# 51-2001-01-16_04_Power_Module_Schematic.net
KiCad netlist of a schematic drawn in Altium Designer
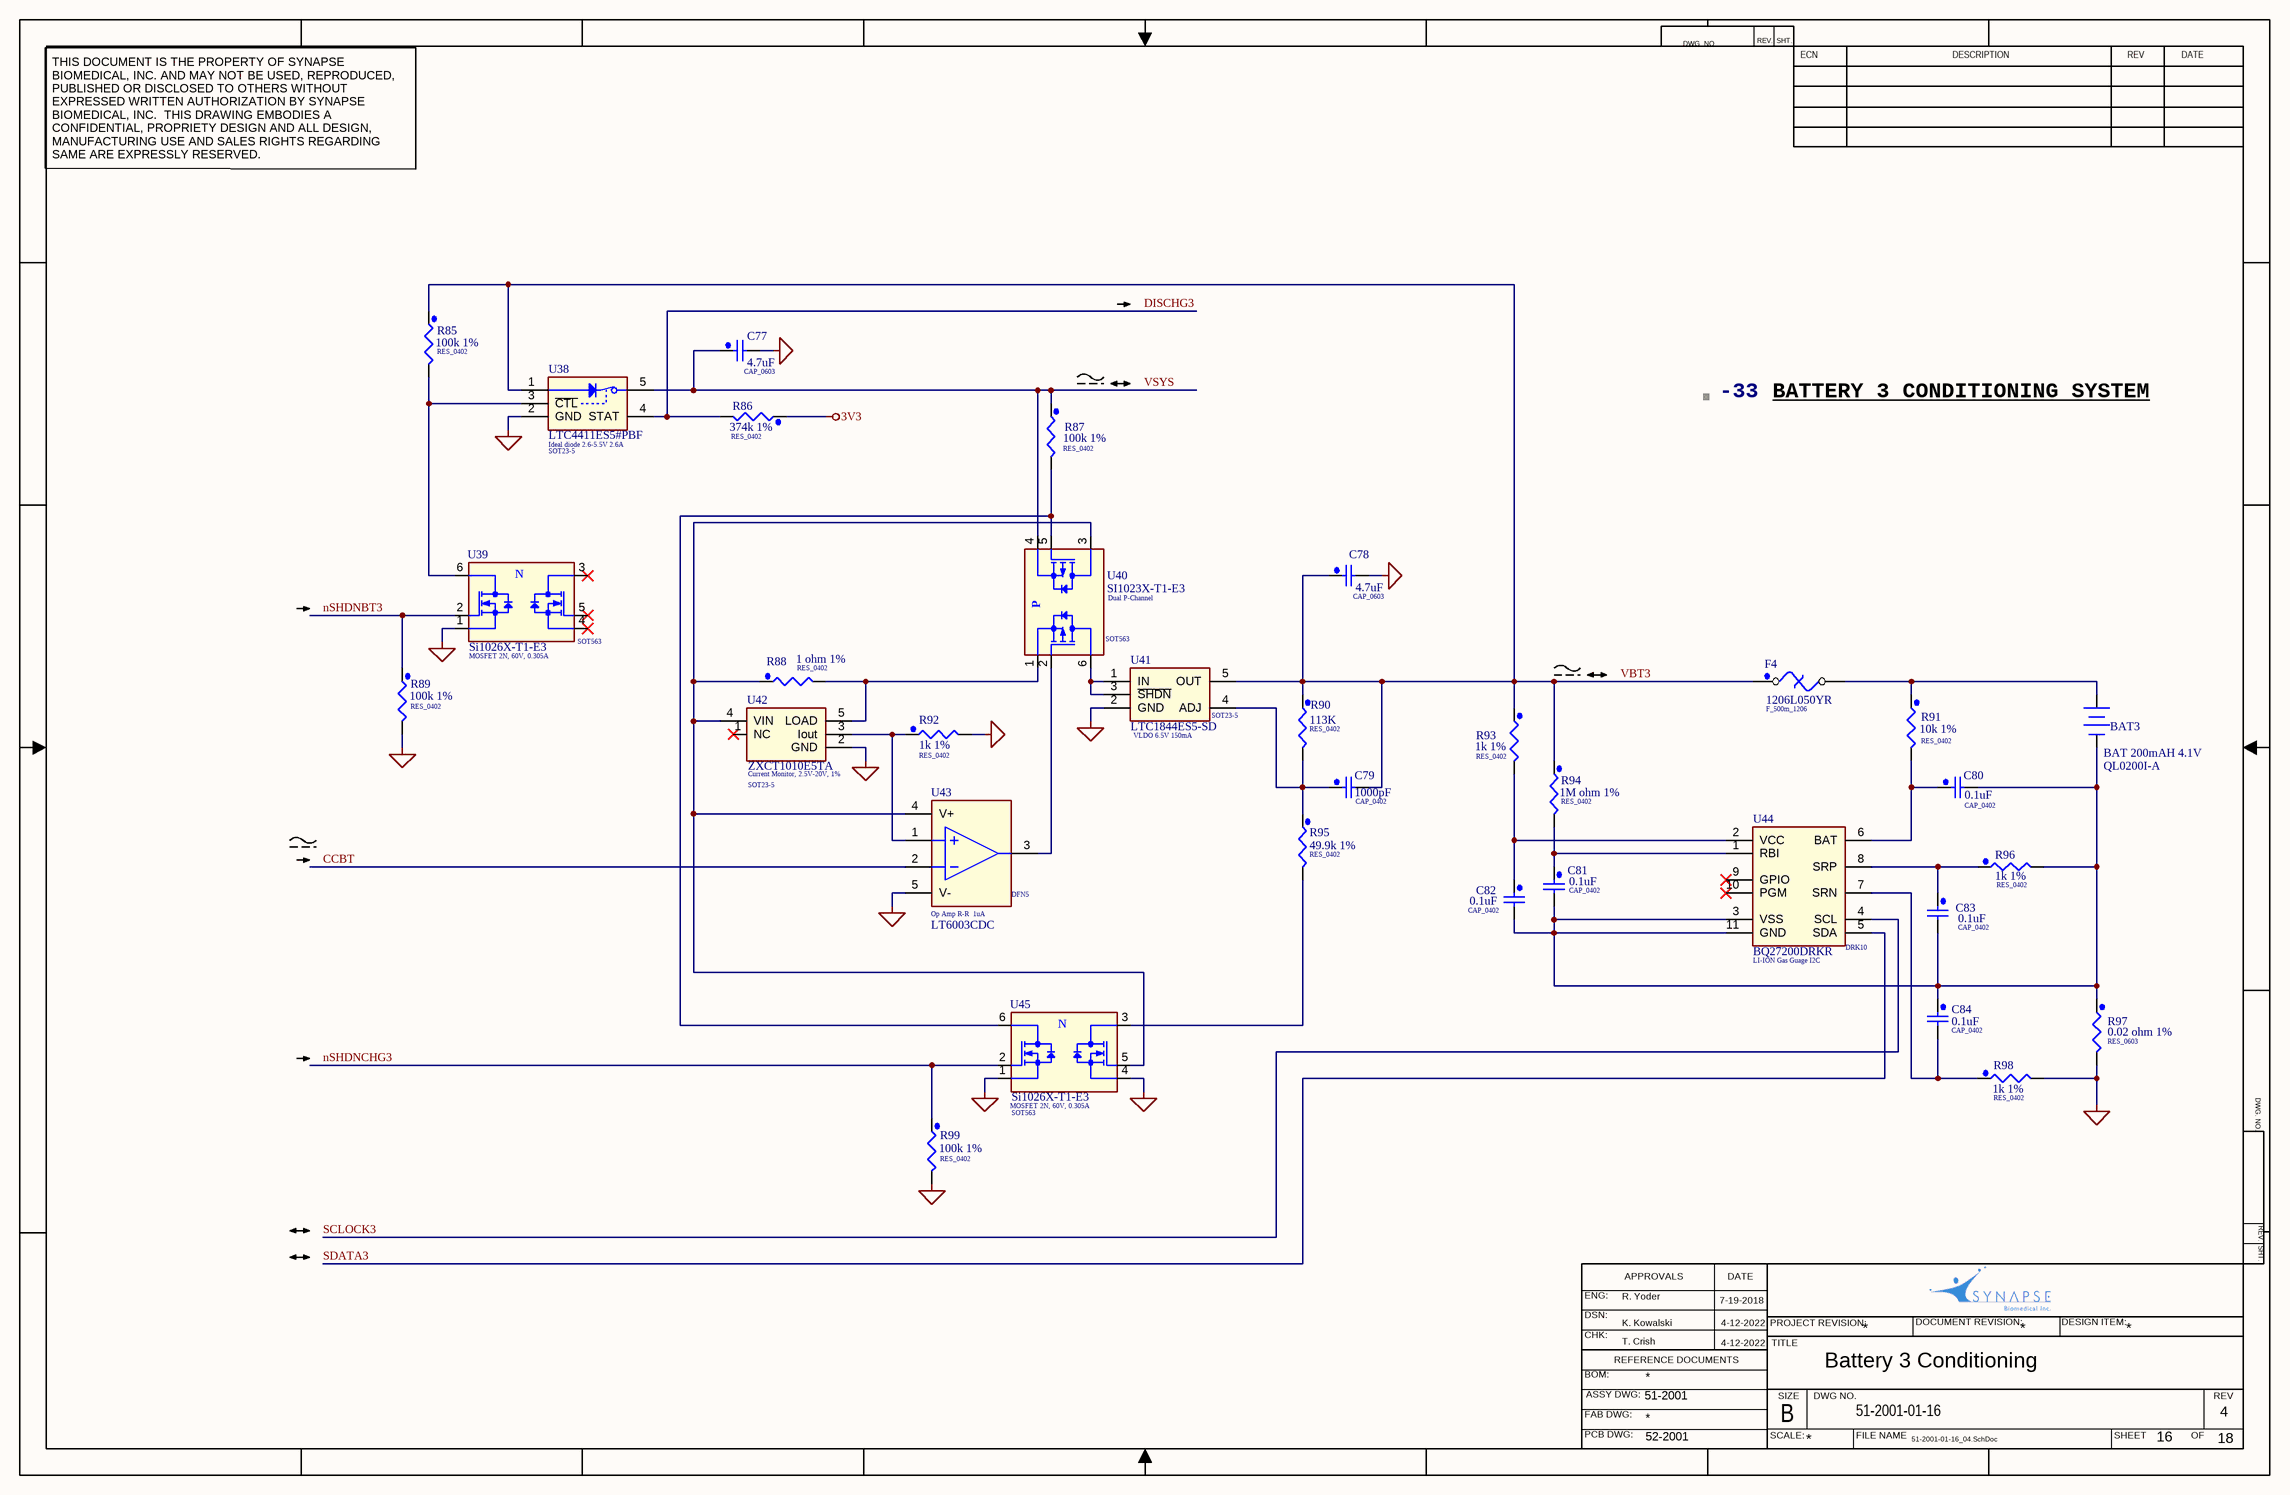
[diagram p0: 51-2001-01-16_04 Power Module Schematic.SchDoc]

(export (version "E")
  (design (tool "Eeschema 10.0.6"))
  (components
    (comp (ref "-33")
      (value "BOM_S1")
      (description "BOM item small graphic")
      (fields (field (name "XDESCRIPTION") "BATTERY 3 CONDITIONING SYSTEM"))
      (libsource (lib "BOM_sym") (part "BOM_S1"))
    )
    (comp (ref "BAT3")
      (value "BAT 200mAH 4.1V")
      (footprint "QL0200I-A")
      (description "Li-ion battery 200mAH 4.1V")
      (fields (field (name "MFR") "Quallion") (field (name "MPN") "QL0200I-A"))
      (libsource (lib "NNPS Integrated Parts") (part "QL0200I-A"))
    )
    (comp (ref "C77")
      (value "4.7uF")
      (footprint "CAP_0603")
      (description "4.7uF, 10V, X5R, 10%, 0603, RoHS")
      (fields
        (field (name "MFR") "Murata Electronics North America")
        (field (name "PACKAGEDESCRIPTION") "CAP_0603")
        (field (name "MPN") "GRM185R61A475KE11D")
      )
      (libsource (lib "NNPS Integrated Parts") (part "LMK107BJ475KA-T"))
    )
    (comp (ref "C78")
      (value "4.7uF")
      (footprint "CAP_0603")
      (description "4.7uF, 10V, X5R, 10%, 0603, RoHS")
      (fields
        (field (name "MFR") "Murata Electronics North America")
        (field (name "PACKAGEDESCRIPTION") "CAP_0603")
        (field (name "MPN") "GRM185R61A475KE11D")
      )
      (libsource (lib "NNPS Integrated Parts") (part "LMK107BJ475KA-T"))
    )
    (comp (ref "C79")
      (value "1000pF")
      (footprint "CAP_0402")
      (description "1000pF, 50V, C0G, 5%, 0402, RoHS")
      (fields
        (field (name "MFR") "Murata")
        (field (name "PACKAGEDESCRIPTION") "CAP_0402")
        (field (name "MPN") "GRM1555C1H102JA01D")
      )
      (libsource (lib "NNPS Integrated Parts") (part "GRM1555C1H102JA01D"))
    )
    (comp (ref "C80")
      (value "0.1uF")
      (footprint "CAP_0402")
      (description "0.1uF, 16V, X7R, 0402, RoHS")
      (fields
        (field (name "MFR") "Murata")
        (field (name "PACKAGEDESCRIPTION") "CAP_0402")
        (field (name "MPN") "GRM155R71C104KA88D")
      )
      (libsource (lib "NNPS Integrated Parts") (part "GRM155R71C104KA88D"))
    )
    (comp (ref "C81")
      (value "0.1uF")
      (footprint "CAP_0402")
      (description "0.1uF, 16V, X7R, 0402, RoHS")
      (fields
        (field (name "MFR") "Murata")
        (field (name "PACKAGEDESCRIPTION") "CAP_0402")
        (field (name "MPN") "GRM155R71C104KA88D")
      )
      (libsource (lib "NNPS Integrated Parts") (part "GRM155R71C104KA88D"))
    )
    (comp (ref "C82")
      (value "0.1uF")
      (footprint "CAP_0402")
      (description "0.1uF, 16V, X7R, 0402, RoHS")
      (fields
        (field (name "MFR") "Murata")
        (field (name "PACKAGEDESCRIPTION") "CAP_0402")
        (field (name "MPN") "GRM155R71C104KA88D")
      )
      (libsource (lib "NNPS Integrated Parts") (part "GRM155R71C104KA88D"))
    )
    (comp (ref "C83")
      (value "0.1uF")
      (footprint "CAP_0402")
      (description "0.1uF, 16V, X7R, 0402, RoHS")
      (fields
        (field (name "MFR") "Murata")
        (field (name "PACKAGEDESCRIPTION") "CAP_0402")
        (field (name "MPN") "GRM155R71C104KA88D")
      )
      (libsource (lib "NNPS Integrated Parts") (part "GRM155R71C104KA88D"))
    )
    (comp (ref "C84")
      (value "0.1uF")
      (footprint "CAP_0402")
      (description "0.1uF, 16V, X7R, 0402, RoHS")
      (fields
        (field (name "MFR") "Murata")
        (field (name "PACKAGEDESCRIPTION") "CAP_0402")
        (field (name "MPN") "GRM155R71C104KA88D")
      )
      (libsource (lib "NNPS Integrated Parts") (part "GRM155R71C104KA88D"))
    )
    (comp (ref "F4")
      (value "F_500m_1206")
      (footprint "FUSE_1206")
      (description "PTC Resettable, 500mA, 0.4 ohm,  6V, 1206, RoHS")
      (fields
        (field (name "MFR") "Littelfuse")
        (field (name "PACKAGEDESCRIPTION") "F_500m_1206")
        (field (name "MPN") "1206L050YR")
      )
      (libsource (lib "NNPS Integrated Parts") (part "1206L050YR"))
    )
    (comp (ref "R85")
      (value "100k 1%")
      (footprint "RES_0402")
      (description "100k ohm, 1%, 1/16W, smd, 0402, RoHS")
      (fields
        (field (name "MFR") "Vishay Dale")
        (field (name "PACKAGEDESCRIPTION") "RES_0402")
        (field (name "MPN") "CRCW0402100KFKED")
      )
      (libsource (lib "NNPS Integrated Parts") (part "MCR01MZPF1003"))
    )
    (comp (ref "R86")
      (value "374k 1%")
      (footprint "RES_0402")
      (description "374k ohm, 1%, 1/16W, 0402,RoHS")
      (fields
        (field (name "MFR") "Vishay Dale")
        (field (name "PACKAGEDESCRIPTION") "RES_0402")
        (field (name "MPN") "CRCW0402374KFKED")
      )
      (libsource (lib "NNPS Integrated Parts") (part "CRCW0402374KFKED"))
    )
    (comp (ref "R87")
      (value "100k 1%")
      (footprint "RES_0402")
      (description "100k ohm, 1%, 1/16W, smd, 0402, RoHS")
      (fields
        (field (name "MFR") "Vishay Dale")
        (field (name "PACKAGEDESCRIPTION") "RES_0402")
        (field (name "MPN") "CRCW0402100KFKED")
      )
      (libsource (lib "NNPS Integrated Parts") (part "MCR01MZPF1003"))
    )
    (comp (ref "R88")
      (value "1 ohm 1%")
      (footprint "RES_0402")
      (description "1.0 ohm, 1%, 1/16W, 0402, RoHS")
      (fields
        (field (name "MFR") "Vishay Dale")
        (field (name "PACKAGEDESCRIPTION") "RES_0402")
        (field (name "MPN") "CRCW04021R00FNED")
      )
      (libsource (lib "NNPS Integrated Parts") (part "CRCW04021R00FNED"))
    )
    (comp (ref "R89")
      (value "100k 1%")
      (footprint "RES_0402")
      (description "100k ohm, 1%, 1/16W, smd, 0402, RoHS")
      (fields
        (field (name "MFR") "Vishay Dale")
        (field (name "PACKAGEDESCRIPTION") "RES_0402")
        (field (name "MPN") "CRCW0402100KFKED")
      )
      (libsource (lib "NNPS Integrated Parts") (part "MCR01MZPF1003"))
    )
    (comp (ref "R90")
      (value "113K")
      (footprint "RES_0402")
      (description "113k ohm, 1%, 1/16W, 0402, RoHS")
      (fields
        (field (name "MFR") "Vishay Dale")
        (field (name "PACKAGEDESCRIPTION") "RES_0402")
        (field (name "MPN") "CRCW0402113KFKED")
      )
      (libsource (lib "NNPS Integrated Parts") (part "ERJ-2RKF1133X"))
    )
    (comp (ref "R91")
      (value "10k 1%")
      (footprint "RES_0402")
      (description "10.0k ohm, 1%, 1/16W, smd, 0402, RoHS")
      (fields
        (field (name "MFR") "Vishay Dale")
        (field (name "PACKAGEDESCRIPTION") "RES_0402")
        (field (name "MPN") "CRCW040210K0FKED")
      )
      (libsource (lib "NNPS Integrated Parts") (part "MCR01MZPF1002"))
    )
    (comp (ref "R92")
      (value "1k 1%")
      (footprint "RES_0402")
      (description "1.0k ohm 1% 1/16W smd 0402 RoHS")
      (fields
        (field (name "MFR") "Vishay Dale")
        (field (name "PACKAGEDESCRIPTION") "RES_0402")
        (field (name "MPN") "CRCW04021K00FKED")
      )
      (libsource (lib "NNPS Integrated Parts") (part "MCR01MZPF1001"))
    )
    (comp (ref "R93")
      (value "1k 1%")
      (footprint "RES_0402")
      (description "1.0k ohm 1% 1/16W smd 0402 RoHS")
      (fields
        (field (name "MFR") "Vishay Dale")
        (field (name "PACKAGEDESCRIPTION") "RES_0402")
        (field (name "MPN") "CRCW04021K00FKED")
      )
      (libsource (lib "NNPS Integrated Parts") (part "MCR01MZPF1001"))
    )
    (comp (ref "R94")
      (value "1M ohm 1%")
      (footprint "RES_0402")
      (description "1M ohm, 1/16W, 1%, 0402, RoHS")
      (fields
        (field (name "MFR") "Vishay Dale")
        (field (name "PACKAGEDESCRIPTION") "RES_0402")
        (field (name "MPN") "CRCW04021M00FKED")
      )
      (libsource (lib "NNPS Integrated Parts") (part "MCR01MZPF1004"))
    )
    (comp (ref "R95")
      (value "49.9k 1%")
      (footprint "RES_0402")
      (description "49.9k ohm, 1%, 1/16W, 0402, RoHS")
      (fields
        (field (name "MFR") "Vishay Dale")
        (field (name "PACKAGEDESCRIPTION") "RES_0402")
        (field (name "MPN") "CRCW040249K9FKED")
      )
      (libsource (lib "NNPS Integrated Parts") (part "MCR01MZPF4992"))
    )
    (comp (ref "R96")
      (value "1k 1%")
      (footprint "RES_0402")
      (description "1.0k ohm 1% 1/16W smd 0402 RoHS")
      (fields
        (field (name "MFR") "Vishay Dale")
        (field (name "PACKAGEDESCRIPTION") "RES_0402")
        (field (name "MPN") "CRCW04021K00FKED")
      )
      (libsource (lib "NNPS Integrated Parts") (part "MCR01MZPF1001"))
    )
    (comp (ref "R97")
      (value "0.02 ohm 1%")
      (footprint "RES_0603")
      (description "0.02 ohm, 1%, 1/10W, 0603, RoHS")
      (fields
        (field (name "MFR") "Vishay Dale")
        (field (name "PACKAGEDESCRIPTION") "RES_0603")
        (field (name "MPN") "WSL0603R0200FEA")
      )
      (libsource (lib "NNPS Integrated Parts") (part "WSL0603R0200FEA"))
    )
    (comp (ref "R98")
      (value "1k 1%")
      (footprint "RES_0402")
      (description "1.0k ohm 1% 1/16W smd 0402 RoHS")
      (fields
        (field (name "MFR") "Vishay Dale")
        (field (name "PACKAGEDESCRIPTION") "RES_0402")
        (field (name "MPN") "CRCW04021K00FKED")
      )
      (libsource (lib "NNPS Integrated Parts") (part "MCR01MZPF1001"))
    )
    (comp (ref "R99")
      (value "100k 1%")
      (footprint "RES_0402")
      (description "100k ohm, 1%, 1/16W, smd, 0402, RoHS")
      (fields
        (field (name "MFR") "Vishay Dale")
        (field (name "PACKAGEDESCRIPTION") "RES_0402")
        (field (name "MPN") "CRCW0402100KFKED")
      )
      (libsource (lib "NNPS Integrated Parts") (part "MCR01MZPF1003"))
    )
    (comp (ref "U38")
      (value "Ideal diode 2.6-5.5V 2.6A")
      (footprint "SOT23-5")
      (description "Ideal diode, 2.6-5.5V, 2.6A, SOT23-5, RoHS")
      (fields
        (field (name "MFR") "Linear Technology")
        (field (name "PACKAGEDESCRIPTION") "SOT23-5")
        (field (name "MPN") "LTC4411ES5#PBF")
      )
      (libsource (lib "NNPS Integrated Parts") (part "LTC4411ES5"))
    )
    (comp (ref "U39")
      (value "MOSFET 2N, 60V, 0.305A")
      (footprint "SOT-563")
      (description "MOSFET 2N, 60V, 0.305A, RoHS")
      (fields
        (field (name "MFR") "Vishay Siliconix")
        (field (name "PACKAGEDESCRIPTION") "SOT563")
        (field (name "MPN") "Si1026X-T1-E3")
      )
      (libsource (lib "NNPS Integrated Parts") (part "Si1026X-T1-E3"))
    )
    (comp (ref "U40")
      (value "Dual P-Channel")
      (footprint "SOT-563")
      (description "Dual P-Channel Mosfet, SOT563, RoHS")
      (fields
        (field (name "MFR") "Vishay Siliconix")
        (field (name "PACKAGEDESCRIPTION") "SOT563")
        (field (name "MPN") "SI1023X-T1-E3")
      )
      (libsource (lib "NNPS Integrated Parts") (part "SI1023X-T1-E3"))
    )
    (comp (ref "U41")
      (value "VLDO 6.5V 150mA")
      (footprint "SOT23-5")
      (description "VLDO, 150mA, SOT23-5, RoHS")
      (fields
        (field (name "MFR") "Linear Technology")
        (field (name "PACKAGEDESCRIPTION") "SOT23-5")
        (field (name "MPN") "LTC1844ES5-SD")
      )
      (libsource (lib "NNPS Integrated Parts") (part "LTC1844ES5-SD"))
    )
    (comp (ref "U42")
      (value "Current Monitor, 2.5V-20V, 1%")
      (footprint "SOT23-5")
      (description "Current Monitor, 2.5V-20V, 1%, RoHS")
      (fields
        (field (name "MFR") "Diodes Incorporated")
        (field (name "PACKAGEDESCRIPTION") "SOT23-5")
        (field (name "MPN") "ZXCT1010E5TA")
      )
      (libsource (lib "NNPS Integrated Parts") (part "ZXCT1010E5TA"))
    )
    (comp (ref "U43")
      (value "Op Amp R-R  1uA")
      (footprint "DFN4")
      (description "Op Amp, R-R, 1uA, RoHS")
      (fields
        (field (name "PACKAGEDESCRIPTION") "DFN5")
        (field (name "MFR") "Linear Technology")
        (field (name "MPN") "LT6003CDC")
      )
      (libsource (lib "NNPS Integrated Parts") (part "LT6003CDC"))
    )
    (comp (ref "U44")
      (value "LI-ION Gas Guage I2C")
      (footprint "QFN10")
      (description "LI-ION Gas Guage, I2C, QFN10, RoHS")
      (fields
        (field (name "MFR") "Texas Instruments")
        (field (name "PACKAGEDESCRIPTION") "DRK10")
        (field (name "MPN") "BQ27200DRKR")
      )
      (libsource (lib "NNPS Integrated Parts") (part "BQ27200DRKR"))
    )
    (comp (ref "U45")
      (value "MOSFET 2N, 60V, 0.305A")
      (footprint "SOT-563")
      (description "MOSFET 2N, 60V, 0.305A, RoHS")
      (fields
        (field (name "MFR") "Vishay Siliconix")
        (field (name "PACKAGEDESCRIPTION") "SOT563")
        (field (name "MPN") "Si1026X-T1-E3")
      )
      (libsource (lib "NNPS Integrated Parts") (part "Si1026X-T1-E3"))
    )
  )
  (nets
    (net (code "1") (name "/CCBT") (class "Default")
      (node (ref "U43") (pin "2") (pinfunction "-IN_2") (pintype "passive"))
    )
    (net (code "2") (name "/DISCHG3") (class "Default")
      (node (ref "R86") (pin "2") (pinfunction "2_2") (pintype "passive"))
      (node (ref "U38") (pin "4") (pinfunction "STAT_4") (pintype "passive"))
    )
    (net (code "3") (name "/SCLOCK3") (class "Default")
      (node (ref "U44") (pin "4") (pinfunction "SCL_4") (pintype "passive"))
    )
    (net (code "4") (name "/SDATA3") (class "Default")
      (node (ref "U44") (pin "5") (pinfunction "SDA_5") (pintype "passive"))
    )
    (net (code "5") (name "/VBT3") (class "Default")
      (node (ref "C78") (pin "1") (pinfunction "1_1") (pintype "passive"))
      (node (ref "C79") (pin "2") (pinfunction "2_2") (pintype "passive"))
      (node (ref "F4") (pin "1") (pinfunction "1_1") (pintype "passive"))
      (node (ref "R85") (pin "1") (pinfunction "1_1") (pintype "passive"))
      (node (ref "R90") (pin "1") (pinfunction "1_1") (pintype "passive"))
      (node (ref "R93") (pin "1") (pinfunction "1_1") (pintype "passive"))
      (node (ref "R94") (pin "1") (pinfunction "1_1") (pintype "passive"))
      (node (ref "U38") (pin "1") (pinfunction "IN_1") (pintype "passive"))
      (node (ref "U41") (pin "5") (pinfunction "OUT_5") (pintype "passive"))
    )
    (net (code "6") (name "/VSYS") (class "Default")
      (node (ref "C77") (pin "1") (pinfunction "1_1") (pintype "passive"))
      (node (ref "R87") (pin "1") (pinfunction "1_1") (pintype "passive"))
      (node (ref "U38") (pin "5") (pinfunction "OUT_5") (pintype "passive"))
      (node (ref "U40") (pin "4") (pinfunction "S2_4") (pintype "passive"))
    )
    (net (code "7") (name "/nSHDNBT3") (class "Default")
      (node (ref "R89") (pin "1") (pinfunction "1_1") (pintype "passive"))
      (node (ref "U39") (pin "2") (pinfunction "G1_2") (pintype "passive"))
    )
    (net (code "8") (name "/nSHDNCHG3") (class "Default")
      (node (ref "R99") (pin "1") (pinfunction "1_1") (pintype "passive"))
      (node (ref "U45") (pin "2") (pinfunction "G1_2") (pintype "passive"))
    )
    (net (code "9") (name "3V3") (class "Default")
      (node (ref "R86") (pin "1") (pinfunction "1_1") (pintype "passive"))
    )
    (net (code "10") (name "<NO NET>") (class "Default")
      (node (ref "R99") (pin "2") (pinfunction "2_2") (pintype "passive"))
    )
    (net (code "11") (name "GND") (class "Default")
      (node (ref "C77") (pin "2") (pinfunction "2_2") (pintype "passive"))
      (node (ref "C78") (pin "2") (pinfunction "2_2") (pintype "passive"))
      (node (ref "R89") (pin "2") (pinfunction "2_2") (pintype "passive"))
      (node (ref "R92") (pin "2") (pinfunction "2_2") (pintype "passive"))
      (node (ref "R97") (pin "2") (pinfunction "2_2") (pintype "passive"))
      (node (ref "R98") (pin "2") (pinfunction "2_2") (pintype "passive"))
      (node (ref "U38") (pin "2") (pinfunction "GND_2") (pintype "passive"))
      (node (ref "U39") (pin "1") (pinfunction "S1_1") (pintype "passive"))
      (node (ref "U41") (pin "2") (pinfunction "GND_2") (pintype "passive"))
      (node (ref "U42") (pin "2") (pinfunction "GND_2") (pintype "power_in"))
      (node (ref "U43") (pin "5") (pinfunction "V-_5") (pintype "power_in"))
      (node (ref "U45") (pin "1") (pinfunction "S1_1") (pintype "passive"))
      (node (ref "U45") (pin "4") (pinfunction "S2_4") (pintype "passive"))
    )
    (net (code "12") (name "Net-(BAT3-+)") (class "Default")
      (node (ref "BAT3") (pin "1") (pinfunction "+_1") (pintype "passive"))
      (node (ref "F4") (pin "2") (pinfunction "2_2") (pintype "passive"))
      (node (ref "R91") (pin "1") (pinfunction "1_1") (pintype "passive"))
    )
    (net (code "13") (name "Net-(BAT3--)") (class "Default")
      (node (ref "BAT3") (pin "2") (pinfunction "-_2") (pintype "passive"))
      (node (ref "C80") (pin "2") (pinfunction "2_2") (pintype "passive"))
      (node (ref "C81") (pin "2") (pinfunction "2_2") (pintype "passive"))
      (node (ref "C82") (pin "2") (pinfunction "2_2") (pintype "passive"))
      (node (ref "C83") (pin "2") (pinfunction "2_2") (pintype "passive"))
      (node (ref "C84") (pin "1") (pinfunction "1_1") (pintype "passive"))
      (node (ref "R96") (pin "2") (pinfunction "2_2") (pintype "passive"))
      (node (ref "R97") (pin "1") (pinfunction "1_1") (pintype "passive"))
      (node (ref "U44") (pin "11") (pinfunction "GND_11") (pintype "passive"))
      (node (ref "U44") (pin "3") (pinfunction "VSS_3") (pintype "passive"))
    )
    (net (code "14") (name "Net-(U38-~{CTL})") (class "Default")
      (node (ref "R85") (pin "2") (pinfunction "2_2") (pintype "passive"))
      (node (ref "U38") (pin "3") (pinfunction "~{CTL}_3") (pintype "passive"))
      (node (ref "U39") (pin "6") (pinfunction "D1_6") (pintype "passive"))
    )
    (net (code "15") (name "Net-(U40-D1)") (class "Default")
      (node (ref "U40") (pin "6") (pinfunction "D1_6") (pintype "passive"))
      (node (ref "U41") (pin "1") (pinfunction "IN_1") (pintype "passive"))
      (node (ref "U41") (pin "3") (pinfunction "SHDN_3") (pintype "passive"))
    )
    (net (code "16") (name "Net-(U40-D2)") (class "Default")
      (node (ref "R88") (pin "1") (pinfunction "1_1") (pintype "passive"))
      (node (ref "U40") (pin "3") (pinfunction "D2_3") (pintype "passive"))
      (node (ref "U42") (pin "4") (pinfunction "VIN_4") (pintype "power_in"))
      (node (ref "U43") (pin "4") (pinfunction "V+_4") (pintype "power_in"))
      (node (ref "U45") (pin "5") (pinfunction "G2_5") (pintype "passive"))
    )
    (net (code "17") (name "Net-(U40-G1)") (class "Default")
      (node (ref "U40") (pin "2") (pinfunction "G1_2") (pintype "passive"))
      (node (ref "U43") (pin "3") (pinfunction "OUT_A_3") (pintype "passive"))
    )
    (net (code "18") (name "Net-(U40-G2)") (class "Default")
      (node (ref "R87") (pin "2") (pinfunction "2_2") (pintype "passive"))
      (node (ref "U40") (pin "5") (pinfunction "G2_5") (pintype "passive"))
      (node (ref "U45") (pin "6") (pinfunction "D1_6") (pintype "passive"))
    )
    (net (code "19") (name "Net-(U40-S1)") (class "Default")
      (node (ref "R88") (pin "2") (pinfunction "2_2") (pintype "passive"))
      (node (ref "U40") (pin "1") (pinfunction "S1_1") (pintype "passive"))
      (node (ref "U42") (pin "5") (pinfunction "LOAD_5") (pintype "passive"))
    )
    (net (code "20") (name "Net-(U41-ADJ)") (class "Default")
      (node (ref "C79") (pin "1") (pinfunction "1_1") (pintype "passive"))
      (node (ref "R90") (pin "2") (pinfunction "2_2") (pintype "passive"))
      (node (ref "R95") (pin "1") (pinfunction "1_1") (pintype "passive"))
      (node (ref "U41") (pin "4") (pinfunction "ADJ_4") (pintype "passive"))
    )
    (net (code "21") (name "Net-(U42-Iout)") (class "Default")
      (node (ref "R92") (pin "1") (pinfunction "1_1") (pintype "passive"))
      (node (ref "U42") (pin "3") (pinfunction "Iout_3") (pintype "passive"))
      (node (ref "U43") (pin "1") (pinfunction "+IN_1") (pintype "passive"))
    )
    (net (code "22") (name "Net-(U44-BAT)") (class "Default")
      (node (ref "C80") (pin "1") (pinfunction "1_1") (pintype "passive"))
      (node (ref "R91") (pin "2") (pinfunction "2_2") (pintype "passive"))
      (node (ref "U44") (pin "6") (pinfunction "BAT_6") (pintype "passive"))
    )
    (net (code "23") (name "Net-(U44-RBI)") (class "Default")
      (node (ref "C81") (pin "1") (pinfunction "1_1") (pintype "passive"))
      (node (ref "R94") (pin "2") (pinfunction "2_2") (pintype "passive"))
      (node (ref "U44") (pin "1") (pinfunction "RBI_1") (pintype "passive"))
    )
    (net (code "24") (name "Net-(U44-SRN)") (class "Default")
      (node (ref "C84") (pin "2") (pinfunction "2_2") (pintype "passive"))
      (node (ref "R98") (pin "1") (pinfunction "1_1") (pintype "passive"))
      (node (ref "U44") (pin "7") (pinfunction "SRN_7") (pintype "passive"))
    )
    (net (code "25") (name "Net-(U44-SRP)") (class "Default")
      (node (ref "C83") (pin "1") (pinfunction "1_1") (pintype "passive"))
      (node (ref "R96") (pin "1") (pinfunction "1_1") (pintype "passive"))
      (node (ref "U44") (pin "8") (pinfunction "SRP_8") (pintype "passive"))
    )
    (net (code "26") (name "Net-(U44-VCC)") (class "Default")
      (node (ref "C82") (pin "1") (pinfunction "1_1") (pintype "passive"))
      (node (ref "R93") (pin "2") (pinfunction "2_2") (pintype "passive"))
      (node (ref "U44") (pin "2") (pinfunction "VCC_2") (pintype "passive"))
    )
    (net (code "27") (name "Net-(U45-D2)") (class "Default")
      (node (ref "R95") (pin "2") (pinfunction "2_2") (pintype "passive"))
      (node (ref "U45") (pin "3") (pinfunction "D2_3") (pintype "passive"))
    )
    (net (code "28") (name "unconnected-(U39-D2-Pad3)") (class "Default")
      (node (ref "U39") (pin "3") (pinfunction "D2_3") (pintype "passive+no_connect"))
    )
    (net (code "29") (name "unconnected-(U39-G2-Pad5)") (class "Default")
      (node (ref "U39") (pin "5") (pinfunction "G2_5") (pintype "passive+no_connect"))
    )
    (net (code "30") (name "unconnected-(U39-S2-Pad4)") (class "Default")
      (node (ref "U39") (pin "4") (pinfunction "S2_4") (pintype "passive+no_connect"))
    )
    (net (code "31") (name "unconnected-(U42-NC-Pad1)") (class "Default")
      (node (ref "U42") (pin "1") (pinfunction "NC_1") (pintype "tri_state+no_connect"))
    )
    (net (code "32") (name "unconnected-(U44-GPIO-Pad9)") (class "Default")
      (node (ref "U44") (pin "9") (pinfunction "GPIO_9") (pintype "passive+no_connect"))
    )
    (net (code "33") (name "unconnected-(U44-PGM-Pad10)") (class "Default")
      (node (ref "U44") (pin "10") (pinfunction "PGM_10") (pintype "passive+no_connect"))
    )
  )
)
